# dc25-darknet-dialer.net
KiCad netlist of a schematic drawn in EAGLE
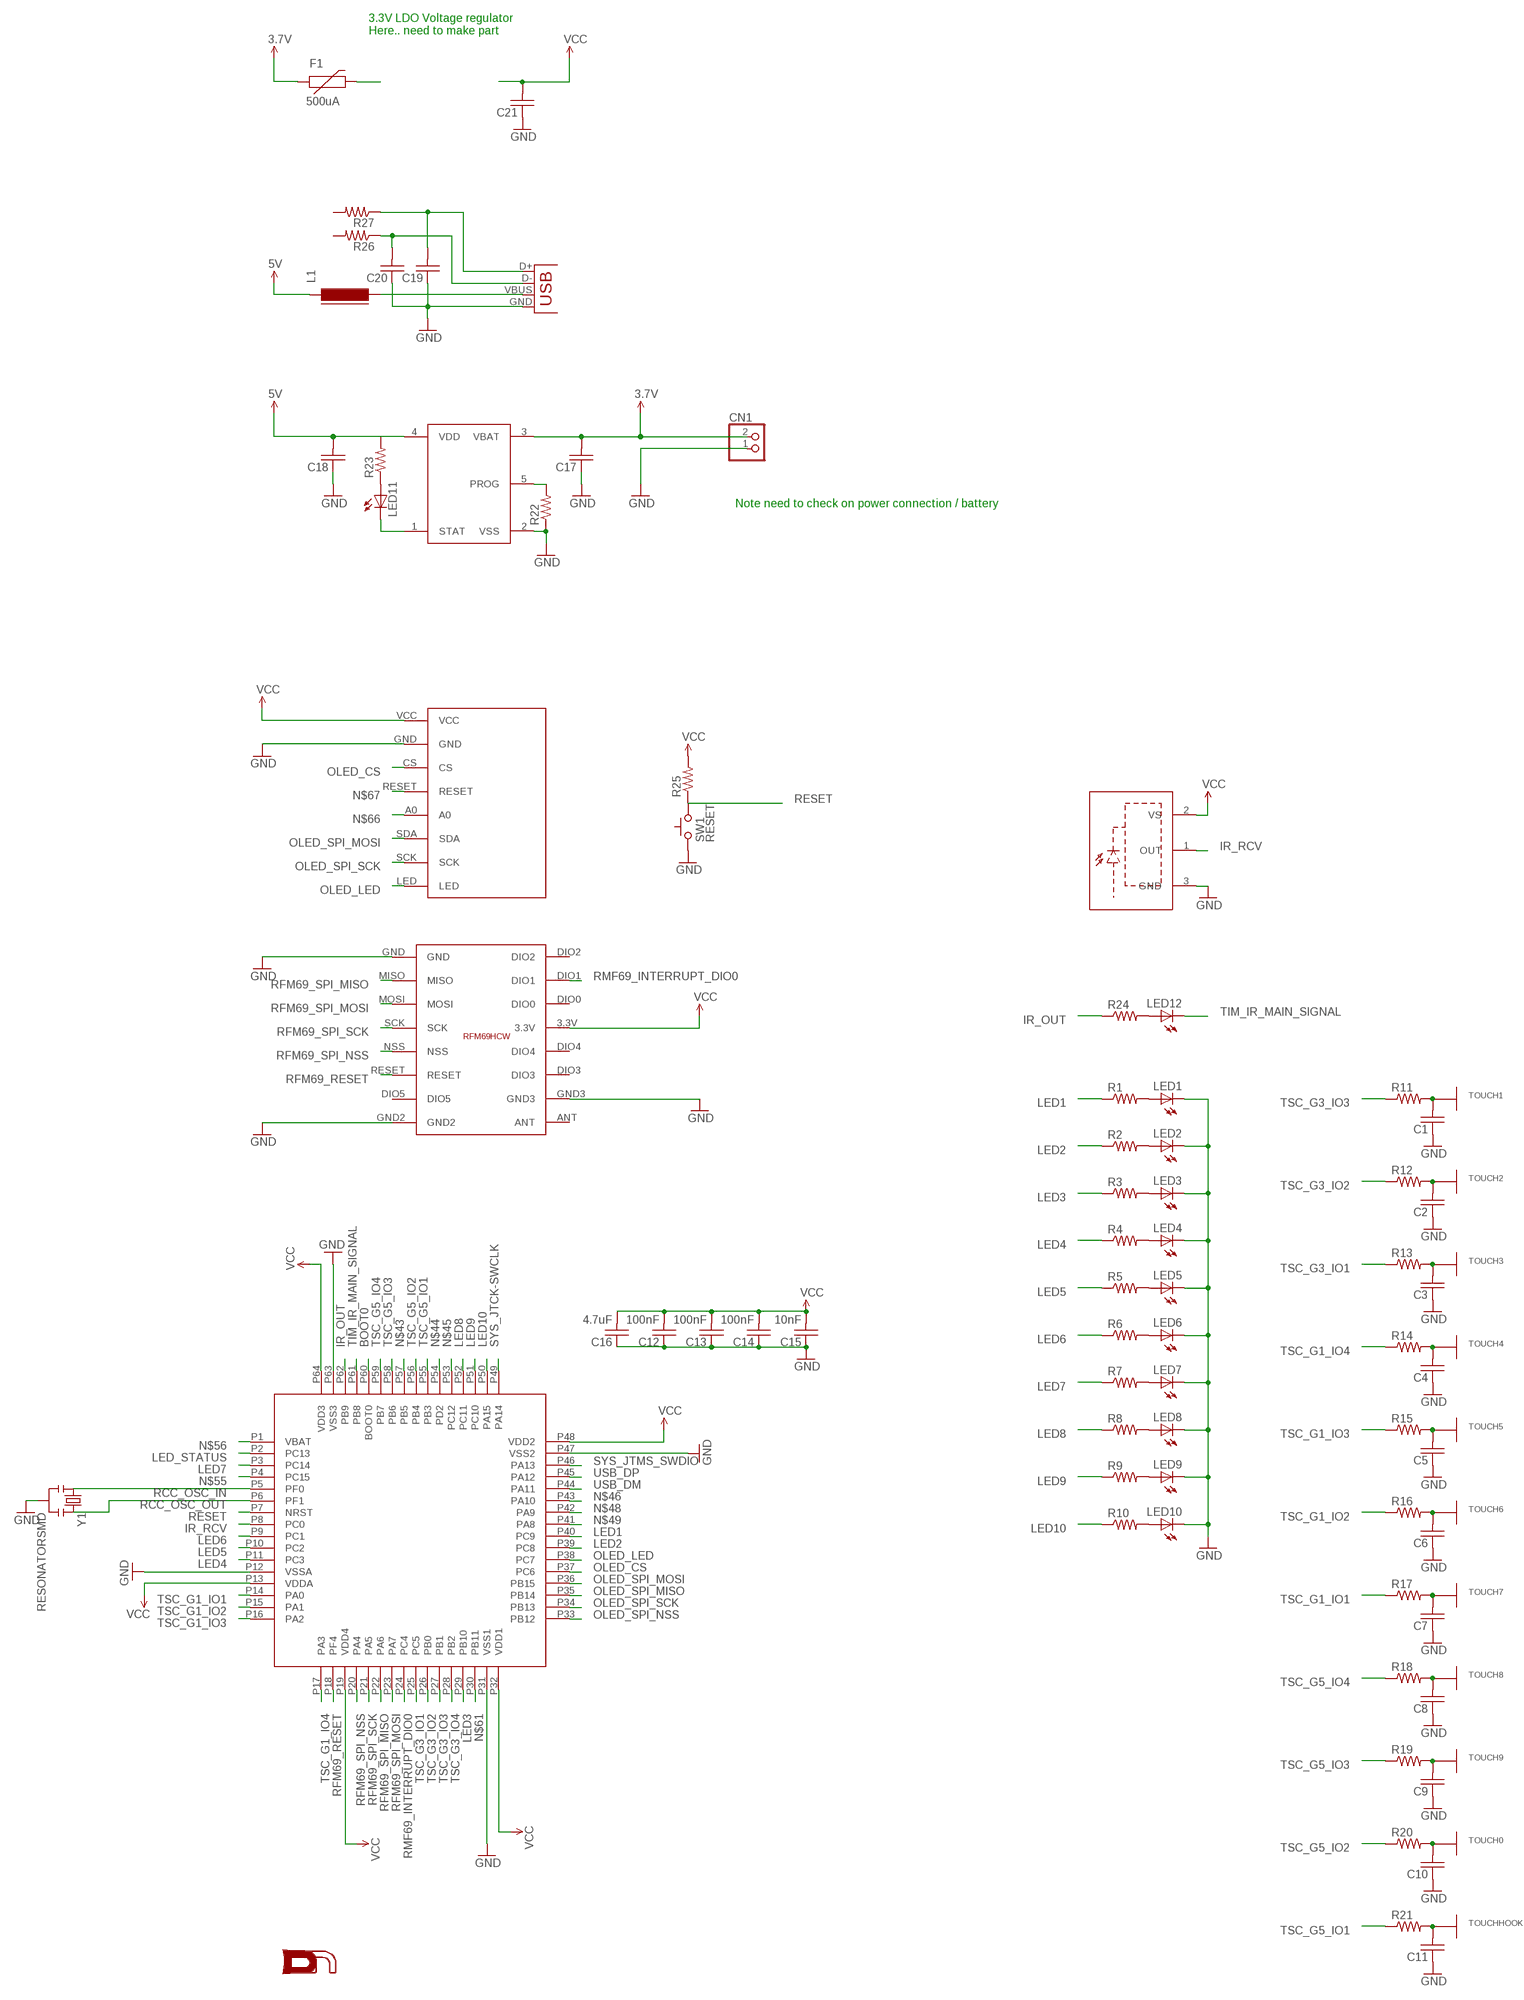
[diagram p0: schematic, sheet 1]

(export (version "E")
  (design (tool "Eeschema 10.0.6"))
  (components
    (comp (ref "C1")
      (value "C-USC0603")
      (footprint "eagle-import:C0603")
      (libsource (lib "eagle-import") (part "C-USC0603"))
    )
    (comp (ref "C2")
      (value "C-USC0603")
      (footprint "eagle-import:C0603")
      (libsource (lib "eagle-import") (part "C-USC0603"))
    )
    (comp (ref "C3")
      (value "C-USC0603")
      (footprint "eagle-import:C0603")
      (libsource (lib "eagle-import") (part "C-USC0603"))
    )
    (comp (ref "C4")
      (value "C-USC0603")
      (footprint "eagle-import:C0603")
      (libsource (lib "eagle-import") (part "C-USC0603"))
    )
    (comp (ref "C5")
      (value "C-USC0603")
      (footprint "eagle-import:C0603")
      (libsource (lib "eagle-import") (part "C-USC0603"))
    )
    (comp (ref "C6")
      (value "C-USC0603")
      (footprint "eagle-import:C0603")
      (libsource (lib "eagle-import") (part "C-USC0603"))
    )
    (comp (ref "C7")
      (value "C-USC0603")
      (footprint "eagle-import:C0603")
      (libsource (lib "eagle-import") (part "C-USC0603"))
    )
    (comp (ref "C8")
      (value "C-USC0603")
      (footprint "eagle-import:C0603")
      (libsource (lib "eagle-import") (part "C-USC0603"))
    )
    (comp (ref "C9")
      (value "C-USC0603")
      (footprint "eagle-import:C0603")
      (libsource (lib "eagle-import") (part "C-USC0603"))
    )
    (comp (ref "C10")
      (value "C-USC0603")
      (footprint "eagle-import:C0603")
      (libsource (lib "eagle-import") (part "C-USC0603"))
    )
    (comp (ref "C11")
      (value "C-USC0603")
      (footprint "eagle-import:C0603")
      (libsource (lib "eagle-import") (part "C-USC0603"))
    )
    (comp (ref "C12")
      (value "100nF")
      (footprint "eagle-import:C0603")
      (libsource (lib "eagle-import") (part "C-USC0603"))
    )
    (comp (ref "C13")
      (value "100nF")
      (footprint "eagle-import:C0603")
      (libsource (lib "eagle-import") (part "C-USC0603"))
    )
    (comp (ref "C14")
      (value "100nF")
      (footprint "eagle-import:C0603")
      (libsource (lib "eagle-import") (part "C-USC0603"))
    )
    (comp (ref "C15")
      (value "10nF")
      (footprint "eagle-import:C0603")
      (libsource (lib "eagle-import") (part "C-USC0603"))
    )
    (comp (ref "C16")
      (value "4.7uF")
      (footprint "eagle-import:C0603")
      (libsource (lib "eagle-import") (part "C-USC0603"))
    )
    (comp (ref "C17")
      (value "C-USC0603")
      (footprint "eagle-import:C0603")
      (libsource (lib "eagle-import") (part "C-USC0603"))
    )
    (comp (ref "C18")
      (value "C-USC0603")
      (footprint "eagle-import:C0603")
      (libsource (lib "eagle-import") (part "C-USC0603"))
    )
    (comp (ref "C19")
      (value "C-USC0603")
      (footprint "eagle-import:C0603")
      (libsource (lib "eagle-import") (part "C-USC0603"))
    )
    (comp (ref "C20")
      (value "C-USC0603")
      (footprint "eagle-import:C0603")
      (libsource (lib "eagle-import") (part "C-USC0603"))
    )
    (comp (ref "C21")
      (value "C-USC0603")
      (footprint "eagle-import:C0603")
      (libsource (lib "eagle-import") (part "C-USC0603"))
    )
    (comp (ref "CN1")
      (value "JST_2PIN-THM-RA")
      (footprint "eagle-import:JST-PH-2-THM-RA")
      (libsource (lib "eagle-import") (part "JST_2PIN-THM-RA"))
    )
    (comp (ref "F1")
      (value "500uA")
      (footprint "eagle-import:PTC-1206")
      (libsource (lib "eagle-import") (part "PTCSMD"))
    )
    (comp (ref "L1")
      (value "FERRITE-0603")
      (footprint "eagle-import:FB603")
      (libsource (lib "eagle-import") (part "FERRITE-0603"))
    )
    (comp (ref "LED1")
      (value "LEDREVERSEMOUNT")
      (footprint "eagle-import:GULLWING_LED")
      (libsource (lib "eagle-import") (part "LEDREVERSEMOUNT"))
    )
    (comp (ref "LED2")
      (value "LEDREVERSEMOUNT")
      (footprint "eagle-import:GULLWING_LED")
      (libsource (lib "eagle-import") (part "LEDREVERSEMOUNT"))
    )
    (comp (ref "LED3")
      (value "LEDREVERSEMOUNT")
      (footprint "eagle-import:GULLWING_LED")
      (libsource (lib "eagle-import") (part "LEDREVERSEMOUNT"))
    )
    (comp (ref "LED4")
      (value "LEDREVERSEMOUNT")
      (footprint "eagle-import:GULLWING_LED")
      (libsource (lib "eagle-import") (part "LEDREVERSEMOUNT"))
    )
    (comp (ref "LED5")
      (value "LEDREVERSEMOUNT")
      (footprint "eagle-import:GULLWING_LED")
      (libsource (lib "eagle-import") (part "LEDREVERSEMOUNT"))
    )
    (comp (ref "LED6")
      (value "LEDREVERSEMOUNT")
      (footprint "eagle-import:GULLWING_LED")
      (libsource (lib "eagle-import") (part "LEDREVERSEMOUNT"))
    )
    (comp (ref "LED7")
      (value "LEDREVERSEMOUNT")
      (footprint "eagle-import:GULLWING_LED")
      (libsource (lib "eagle-import") (part "LEDREVERSEMOUNT"))
    )
    (comp (ref "LED8")
      (value "LEDREVERSEMOUNT")
      (footprint "eagle-import:GULLWING_LED")
      (libsource (lib "eagle-import") (part "LEDREVERSEMOUNT"))
    )
    (comp (ref "LED9")
      (value "LEDREVERSEMOUNT")
      (footprint "eagle-import:GULLWING_LED")
      (libsource (lib "eagle-import") (part "LEDREVERSEMOUNT"))
    )
    (comp (ref "LED10")
      (value "LEDREVERSEMOUNT")
      (footprint "eagle-import:GULLWING_LED")
      (libsource (lib "eagle-import") (part "LEDREVERSEMOUNT"))
    )
    (comp (ref "LED11")
      (value "LED0603")
      (footprint "eagle-import:LED-0603")
      (libsource (lib "eagle-import") (part "LED0603"))
    )
    (comp (ref "LED12")
      (value "LED5MM")
      (footprint "eagle-import:LED5MM")
      (libsource (lib "eagle-import") (part "LED5MM"))
    )
    (comp (ref "R1")
      (value "RESISTOR1206")
      (footprint "eagle-import:1206")
      (libsource (lib "eagle-import") (part "RESISTOR1206"))
    )
    (comp (ref "R2")
      (value "RESISTOR1206")
      (footprint "eagle-import:1206")
      (libsource (lib "eagle-import") (part "RESISTOR1206"))
    )
    (comp (ref "R3")
      (value "RESISTOR1206")
      (footprint "eagle-import:1206")
      (libsource (lib "eagle-import") (part "RESISTOR1206"))
    )
    (comp (ref "R4")
      (value "RESISTOR1206")
      (footprint "eagle-import:1206")
      (libsource (lib "eagle-import") (part "RESISTOR1206"))
    )
    (comp (ref "R5")
      (value "RESISTOR1206")
      (footprint "eagle-import:1206")
      (libsource (lib "eagle-import") (part "RESISTOR1206"))
    )
    (comp (ref "R6")
      (value "RESISTOR1206")
      (footprint "eagle-import:1206")
      (libsource (lib "eagle-import") (part "RESISTOR1206"))
    )
    (comp (ref "R7")
      (value "RESISTOR1206")
      (footprint "eagle-import:1206")
      (libsource (lib "eagle-import") (part "RESISTOR1206"))
    )
    (comp (ref "R8")
      (value "RESISTOR1206")
      (footprint "eagle-import:1206")
      (libsource (lib "eagle-import") (part "RESISTOR1206"))
    )
    (comp (ref "R9")
      (value "RESISTOR1206")
      (footprint "eagle-import:1206")
      (libsource (lib "eagle-import") (part "RESISTOR1206"))
    )
    (comp (ref "R10")
      (value "RESISTOR1206")
      (footprint "eagle-import:1206")
      (libsource (lib "eagle-import") (part "RESISTOR1206"))
    )
    (comp (ref "R11")
      (value "R-US_R0603")
      (footprint "eagle-import:R0603")
      (libsource (lib "eagle-import") (part "R-US_R0603"))
    )
    (comp (ref "R12")
      (value "R-US_R0603")
      (footprint "eagle-import:R0603")
      (libsource (lib "eagle-import") (part "R-US_R0603"))
    )
    (comp (ref "R13")
      (value "R-US_R0603")
      (footprint "eagle-import:R0603")
      (libsource (lib "eagle-import") (part "R-US_R0603"))
    )
    (comp (ref "R14")
      (value "R-US_R0603")
      (footprint "eagle-import:R0603")
      (libsource (lib "eagle-import") (part "R-US_R0603"))
    )
    (comp (ref "R15")
      (value "R-US_R0603")
      (footprint "eagle-import:R0603")
      (libsource (lib "eagle-import") (part "R-US_R0603"))
    )
    (comp (ref "R16")
      (value "R-US_R0603")
      (footprint "eagle-import:R0603")
      (libsource (lib "eagle-import") (part "R-US_R0603"))
    )
    (comp (ref "R17")
      (value "R-US_R0603")
      (footprint "eagle-import:R0603")
      (libsource (lib "eagle-import") (part "R-US_R0603"))
    )
    (comp (ref "R18")
      (value "R-US_R0603")
      (footprint "eagle-import:R0603")
      (libsource (lib "eagle-import") (part "R-US_R0603"))
    )
    (comp (ref "R19")
      (value "R-US_R0603")
      (footprint "eagle-import:R0603")
      (libsource (lib "eagle-import") (part "R-US_R0603"))
    )
    (comp (ref "R20")
      (value "R-US_R0603")
      (footprint "eagle-import:R0603")
      (libsource (lib "eagle-import") (part "R-US_R0603"))
    )
    (comp (ref "R21")
      (value "R-US_R0603")
      (footprint "eagle-import:R0603")
      (libsource (lib "eagle-import") (part "R-US_R0603"))
    )
    (comp (ref "R22")
      (value "R-US_R0603")
      (footprint "eagle-import:R0603")
      (libsource (lib "eagle-import") (part "R-US_R0603"))
    )
    (comp (ref "R23")
      (value "R-US_R0603")
      (footprint "eagle-import:R0603")
      (libsource (lib "eagle-import") (part "R-US_R0603"))
    )
    (comp (ref "R24")
      (value "R-US_0309/12")
      (footprint "eagle-import:0309_12")
      (libsource (lib "eagle-import") (part "R-US_0309/12"))
    )
    (comp (ref "R25")
      (value "R-US_0309/12")
      (footprint "eagle-import:0309_12")
      (libsource (lib "eagle-import") (part "R-US_0309/12"))
    )
    (comp (ref "R26")
      (value "R-US_R0603")
      (footprint "eagle-import:R0603")
      (libsource (lib "eagle-import") (part "R-US_R0603"))
    )
    (comp (ref "R27")
      (value "R-US_R0603")
      (footprint "eagle-import:R0603")
      (libsource (lib "eagle-import") (part "R-US_R0603"))
    )
    (comp (ref "SW1")
      (value "RESET")
      (footprint "eagle-import:TACTILE-2PIN-NARROW")
      (libsource (lib "eagle-import") (part "SWITCH_TACTILETACTILE-2PIN-NARROW"))
    )
    (comp (ref "TOUCH0")
      (value "CAP_TOUCH0")
      (footprint "eagle-import:CAP_TOUCH_PAD_0")
      (libsource (lib "eagle-import") (part "CAP_TOUCH0"))
    )
    (comp (ref "TOUCH1")
      (value "CAP_TOUCH1")
      (footprint "eagle-import:CAP_TOUCH_PAD_1")
      (libsource (lib "eagle-import") (part "CAP_TOUCH1"))
    )
    (comp (ref "TOUCH2")
      (value "CAP_TOUCH2")
      (footprint "eagle-import:CAP_TOUCH_PAD_2")
      (libsource (lib "eagle-import") (part "CAP_TOUCH2"))
    )
    (comp (ref "TOUCH3")
      (value "CAP_TOUCH3")
      (footprint "eagle-import:CAP_TOUCH_PAD_3")
      (libsource (lib "eagle-import") (part "CAP_TOUCH3"))
    )
    (comp (ref "TOUCH4")
      (value "CAP_TOUCH4")
      (footprint "eagle-import:CAP_TOUCH_PAD_4")
      (libsource (lib "eagle-import") (part "CAP_TOUCH4"))
    )
    (comp (ref "TOUCH5")
      (value "CAP_TOUCH5")
      (footprint "eagle-import:CAP_TOUCH_PAD_5")
      (libsource (lib "eagle-import") (part "CAP_TOUCH5"))
    )
    (comp (ref "TOUCH6")
      (value "CAP_TOUCH6")
      (footprint "eagle-import:CAP_TOUCH_PAD_6")
      (libsource (lib "eagle-import") (part "CAP_TOUCH6"))
    )
    (comp (ref "TOUCH7")
      (value "CAP_TOUCH7")
      (footprint "eagle-import:CAP_TOUCH_PAD_7")
      (libsource (lib "eagle-import") (part "CAP_TOUCH7"))
    )
    (comp (ref "TOUCH8")
      (value "CAP_TOUCH8")
      (footprint "eagle-import:CAP_TOUCH_PAD_8")
      (libsource (lib "eagle-import") (part "CAP_TOUCH8"))
    )
    (comp (ref "TOUCH9")
      (value "CAP_TOUCH9")
      (footprint "eagle-import:CAP_TOUCH_PAD_9")
      (libsource (lib "eagle-import") (part "CAP_TOUCH9"))
    )
    (comp (ref "TOUCHHOOK")
      (value "CAP_TOUCHHOOK")
      (footprint "eagle-import:CAP_TOUCH_PAD_HOOK")
      (libsource (lib "eagle-import") (part "CAP_TOUCHHOOK"))
    )
    (comp (ref "U$1")
      (value "DN_LOGO")
      (footprint "eagle-import:DN_LOGO")
      (libsource (lib "eagle-import") (part "DN_LOGO"))
    )
    (comp (ref "U$2")
      (value "STM32F302XC")
      (footprint "eagle-import:LQFP64")
      (libsource (lib "eagle-import") (part "STM32F302XC"))
    )
    (comp (ref "U$11")
      (value "DS21984E")
      (footprint "eagle-import:SOT23-5")
      (libsource (lib "eagle-import") (part "DS21984E"))
    )
    (comp (ref "U$12")
      (value "COLOR_LCD_MODULE")
      (footprint "eagle-import:COLOR_LCD_DISPLAY")
      (libsource (lib "eagle-import") (part "COLOR_LCD_MODULE"))
    )
    (comp (ref "U$15")
      (value "RFM69HCWRFN69HCWSMD")
      (footprint "eagle-import:16PIN-PCB-SMD")
      (libsource (lib "eagle-import") (part "RFM69HCWRFN69HCWSMD"))
    )
    (comp (ref "U$17")
      (value "SOP22")
      (footprint "eagle-import:IR-MODULE")
      (libsource (lib "eagle-import") (part "SOP22"))
    )
    (comp (ref "X1")
      (value "USB-MICROB")
      (footprint "eagle-import:USB-MICROB")
      (libsource (lib "eagle-import") (part "USB-MICROB"))
    )
    (comp (ref "Y1")
      (value "RESONATORSMD")
      (footprint "eagle-import:RESONATOR-SMD")
      (libsource (lib "eagle-import") (part "RESONATORSMD"))
    )
  )
  (nets
    (net (code "1") (name "/BOOT0") (class "Default")
      (node (ref "U$2") (pin "P60") (pinfunction "BOOT0_P60") (pintype "bidirectional"))
    )
    (net (code "2") (name "/IR_OUT") (class "Default")
      (node (ref "R24") (pin "1") (pinfunction "1_1") (pintype "passive"))
      (node (ref "U$2") (pin "P62") (pinfunction "PB9_P62") (pintype "bidirectional"))
    )
    (net (code "3") (name "/IR_RCV") (class "Default")
      (node (ref "U$17") (pin "1") (pinfunction "OUT_1") (pintype "bidirectional"))
      (node (ref "U$2") (pin "P8") (pinfunction "PC0_P8") (pintype "bidirectional"))
    )
    (net (code "4") (name "/LED1") (class "Default")
      (node (ref "R1") (pin "1") (pinfunction "1_1") (pintype "passive"))
      (node (ref "U$2") (pin "P40") (pinfunction "PC9_P40") (pintype "bidirectional"))
    )
    (net (code "5") (name "/LED2") (class "Default")
      (node (ref "R2") (pin "1") (pinfunction "1_1") (pintype "passive"))
      (node (ref "U$2") (pin "P39") (pinfunction "PC8_P39") (pintype "bidirectional"))
    )
    (net (code "6") (name "/LED3") (class "Default")
      (node (ref "R3") (pin "1") (pinfunction "1_1") (pintype "passive"))
      (node (ref "U$2") (pin "P29") (pinfunction "PB10_P29") (pintype "bidirectional"))
    )
    (net (code "7") (name "/LED4") (class "Default")
      (node (ref "R4") (pin "1") (pinfunction "1_1") (pintype "passive"))
      (node (ref "U$2") (pin "P11") (pinfunction "PC3_P11") (pintype "bidirectional"))
    )
    (net (code "8") (name "/LED5") (class "Default")
      (node (ref "R5") (pin "1") (pinfunction "1_1") (pintype "passive"))
      (node (ref "U$2") (pin "P10") (pinfunction "PC2_P10") (pintype "bidirectional"))
    )
    (net (code "9") (name "/LED6") (class "Default")
      (node (ref "R6") (pin "1") (pinfunction "1_1") (pintype "passive"))
      (node (ref "U$2") (pin "P9") (pinfunction "PC1_P9") (pintype "bidirectional"))
    )
    (net (code "10") (name "/LED7") (class "Default")
      (node (ref "R7") (pin "1") (pinfunction "1_1") (pintype "passive"))
      (node (ref "U$2") (pin "P3") (pinfunction "PC14_P3") (pintype "bidirectional"))
    )
    (net (code "11") (name "/LED8") (class "Default")
      (node (ref "R8") (pin "1") (pinfunction "1_1") (pintype "passive"))
      (node (ref "U$2") (pin "P52") (pinfunction "PC11_P52") (pintype "bidirectional"))
    )
    (net (code "12") (name "/LED9") (class "Default")
      (node (ref "R9") (pin "1") (pinfunction "1_1") (pintype "passive"))
      (node (ref "U$2") (pin "P51") (pinfunction "PC10_P51") (pintype "bidirectional"))
    )
    (net (code "13") (name "/LED10") (class "Default")
      (node (ref "R10") (pin "1") (pinfunction "1_1") (pintype "passive"))
      (node (ref "U$2") (pin "P50") (pinfunction "PA15_P50") (pintype "bidirectional"))
    )
    (net (code "14") (name "/LED_STATUS") (class "Default")
      (node (ref "U$2") (pin "P2") (pinfunction "PC13_P2") (pintype "bidirectional"))
    )
    (net (code "15") (name "/N$43") (class "Default")
      (node (ref "U$2") (pin "P57") (pinfunction "PB5_P57") (pintype "bidirectional"))
    )
    (net (code "16") (name "/N$44") (class "Default")
      (node (ref "U$2") (pin "P54") (pinfunction "PD2_P54") (pintype "bidirectional"))
    )
    (net (code "17") (name "/N$45") (class "Default")
      (node (ref "U$2") (pin "P53") (pinfunction "PC12_P53") (pintype "bidirectional"))
    )
    (net (code "18") (name "/N$46") (class "Default")
      (node (ref "U$2") (pin "P43") (pinfunction "PA10_P43") (pintype "bidirectional"))
    )
    (net (code "19") (name "/N$48") (class "Default")
      (node (ref "U$2") (pin "P42") (pinfunction "PA9_P42") (pintype "bidirectional"))
    )
    (net (code "20") (name "/N$49") (class "Default")
      (node (ref "U$2") (pin "P41") (pinfunction "PA8_P41") (pintype "bidirectional"))
    )
    (net (code "21") (name "/N$55") (class "Default")
      (node (ref "U$2") (pin "P4") (pinfunction "PC15_P4") (pintype "bidirectional"))
    )
    (net (code "22") (name "/N$56") (class "Default")
      (node (ref "U$2") (pin "P1") (pinfunction "VBAT_P1") (pintype "bidirectional"))
    )
    (net (code "23") (name "/N$61") (class "Default")
      (node (ref "U$2") (pin "P30") (pinfunction "PB11_P30") (pintype "bidirectional"))
    )
    (net (code "24") (name "/N$66") (class "Default")
      (node (ref "U$12") (pin "A0") (pinfunction "A0_A0") (pintype "bidirectional"))
    )
    (net (code "25") (name "/N$67") (class "Default")
      (node (ref "U$12") (pin "RESET") (pinfunction "RESET_RESET") (pintype "bidirectional"))
    )
    (net (code "26") (name "/OLED_CS") (class "Default")
      (node (ref "U$12") (pin "CS") (pinfunction "CS_CS") (pintype "bidirectional"))
      (node (ref "U$2") (pin "P37") (pinfunction "PC6_P37") (pintype "bidirectional"))
    )
    (net (code "27") (name "/OLED_LED") (class "Default")
      (node (ref "U$12") (pin "LED") (pinfunction "LED_LED") (pintype "bidirectional"))
      (node (ref "U$2") (pin "P38") (pinfunction "PC7_P38") (pintype "bidirectional"))
    )
    (net (code "28") (name "/OLED_SPI_MISO") (class "Default")
      (node (ref "U$2") (pin "P35") (pinfunction "PB14_P35") (pintype "bidirectional"))
    )
    (net (code "29") (name "/OLED_SPI_MOSI") (class "Default")
      (node (ref "U$12") (pin "SDA") (pinfunction "SDA_SDA") (pintype "bidirectional"))
      (node (ref "U$2") (pin "P36") (pinfunction "PB15_P36") (pintype "bidirectional"))
    )
    (net (code "30") (name "/OLED_SPI_NSS") (class "Default")
      (node (ref "U$2") (pin "P33") (pinfunction "PB12_P33") (pintype "bidirectional"))
    )
    (net (code "31") (name "/OLED_SPI_SCK") (class "Default")
      (node (ref "U$12") (pin "SCK") (pinfunction "SCK_SCK") (pintype "bidirectional"))
      (node (ref "U$2") (pin "P34") (pinfunction "PB13_P34") (pintype "bidirectional"))
    )
    (net (code "32") (name "/RCC_OSC_IN") (class "Default")
      (node (ref "U$2") (pin "P5") (pinfunction "PF0_P5") (pintype "bidirectional"))
      (node (ref "Y1") (pin "1") (pinfunction "1_1") (pintype "passive"))
    )
    (net (code "33") (name "/RCC_OSC_OUT") (class "Default")
      (node (ref "U$2") (pin "P6") (pinfunction "PF1_P6") (pintype "bidirectional"))
      (node (ref "Y1") (pin "3") (pinfunction "3_3") (pintype "passive"))
    )
    (net (code "34") (name "/RESET") (class "Default")
      (node (ref "R25") (pin "1") (pinfunction "1_1") (pintype "passive"))
      (node (ref "SW1") (pin "P$1") (pinfunction "A_P$1") (pintype "passive"))
      (node (ref "U$2") (pin "P7") (pinfunction "NRST_P7") (pintype "bidirectional"))
    )
    (net (code "35") (name "/RFM69_RESET") (class "Default")
      (node (ref "U$15") (pin "RESET") (pinfunction "RESET_RESET") (pintype "bidirectional"))
      (node (ref "U$2") (pin "P18") (pinfunction "PF4_P18") (pintype "bidirectional"))
    )
    (net (code "36") (name "/RFM69_SPI_MISO") (class "Default")
      (node (ref "U$15") (pin "MISO") (pinfunction "MISO_MISO") (pintype "bidirectional"))
      (node (ref "U$2") (pin "P22") (pinfunction "PA6_P22") (pintype "bidirectional"))
    )
    (net (code "37") (name "/RFM69_SPI_MOSI") (class "Default")
      (node (ref "U$15") (pin "MOSI") (pinfunction "MOSI_MOSI") (pintype "bidirectional"))
      (node (ref "U$2") (pin "P23") (pinfunction "PA7_P23") (pintype "bidirectional"))
    )
    (net (code "38") (name "/RFM69_SPI_NSS") (class "Default")
      (node (ref "U$15") (pin "NSS") (pinfunction "NSS_NSS") (pintype "bidirectional"))
      (node (ref "U$2") (pin "P20") (pinfunction "PA4_P20") (pintype "bidirectional"))
    )
    (net (code "39") (name "/RFM69_SPI_SCK") (class "Default")
      (node (ref "U$15") (pin "SCK") (pinfunction "SCK_SCK") (pintype "bidirectional"))
      (node (ref "U$2") (pin "P21") (pinfunction "PA5_P21") (pintype "bidirectional"))
    )
    (net (code "40") (name "/RMF69_INTERRUPT_DIO0") (class "Default")
      (node (ref "U$15") (pin "DIO1") (pinfunction "DIO1_DIO1") (pintype "bidirectional"))
      (node (ref "U$2") (pin "P24") (pinfunction "PC4_P24") (pintype "bidirectional"))
    )
    (net (code "41") (name "/SYS_JTCK-SWCLK") (class "Default")
      (node (ref "U$2") (pin "P49") (pinfunction "PA14_P49") (pintype "bidirectional"))
    )
    (net (code "42") (name "/SYS_JTMS_SWDIO") (class "Default")
      (node (ref "U$2") (pin "P46") (pinfunction "PA13_P46") (pintype "bidirectional"))
    )
    (net (code "43") (name "/TIM_IR_MAIN_SIGNAL") (class "Default")
      (node (ref "LED12") (pin "K") (pinfunction "C_K") (pintype "output"))
      (node (ref "U$2") (pin "P61") (pinfunction "PB8_P61") (pintype "bidirectional"))
    )
    (net (code "44") (name "/TSC_G1_IO1") (class "Default")
      (node (ref "R17") (pin "1") (pinfunction "1_1") (pintype "passive"))
      (node (ref "U$2") (pin "P14") (pinfunction "PA0_P14") (pintype "bidirectional"))
    )
    (net (code "45") (name "/TSC_G1_IO2") (class "Default")
      (node (ref "R16") (pin "1") (pinfunction "1_1") (pintype "passive"))
      (node (ref "U$2") (pin "P15") (pinfunction "PA1_P15") (pintype "bidirectional"))
    )
    (net (code "46") (name "/TSC_G1_IO3") (class "Default")
      (node (ref "R15") (pin "1") (pinfunction "1_1") (pintype "passive"))
      (node (ref "U$2") (pin "P16") (pinfunction "PA2_P16") (pintype "bidirectional"))
    )
    (net (code "47") (name "/TSC_G1_IO4") (class "Default")
      (node (ref "R14") (pin "1") (pinfunction "1_1") (pintype "passive"))
      (node (ref "U$2") (pin "P17") (pinfunction "PA3_P17") (pintype "bidirectional"))
    )
    (net (code "48") (name "/TSC_G3_IO1") (class "Default")
      (node (ref "R13") (pin "1") (pinfunction "1_1") (pintype "passive"))
      (node (ref "U$2") (pin "P25") (pinfunction "PC5_P25") (pintype "bidirectional"))
    )
    (net (code "49") (name "/TSC_G3_IO2") (class "Default")
      (node (ref "R12") (pin "1") (pinfunction "1_1") (pintype "passive"))
      (node (ref "U$2") (pin "P26") (pinfunction "PB0_P26") (pintype "bidirectional"))
    )
    (net (code "50") (name "/TSC_G3_IO3") (class "Default")
      (node (ref "R11") (pin "1") (pinfunction "1_1") (pintype "passive"))
      (node (ref "U$2") (pin "P27") (pinfunction "PB1_P27") (pintype "bidirectional"))
    )
    (net (code "51") (name "/TSC_G3_IO4") (class "Default")
      (node (ref "U$2") (pin "P28") (pinfunction "PB2_P28") (pintype "bidirectional"))
    )
    (net (code "52") (name "/TSC_G5_IO1") (class "Default")
      (node (ref "R21") (pin "1") (pinfunction "1_1") (pintype "passive"))
      (node (ref "U$2") (pin "P55") (pinfunction "PB3_P55") (pintype "bidirectional"))
    )
    (net (code "53") (name "/TSC_G5_IO2") (class "Default")
      (node (ref "R20") (pin "1") (pinfunction "1_1") (pintype "passive"))
      (node (ref "U$2") (pin "P56") (pinfunction "PB4_P56") (pintype "bidirectional"))
    )
    (net (code "54") (name "/TSC_G5_IO3") (class "Default")
      (node (ref "R19") (pin "1") (pinfunction "1_1") (pintype "passive"))
      (node (ref "U$2") (pin "P58") (pinfunction "PB6_P58") (pintype "bidirectional"))
    )
    (net (code "55") (name "/TSC_G5_IO4") (class "Default")
      (node (ref "R18") (pin "1") (pinfunction "1_1") (pintype "passive"))
      (node (ref "U$2") (pin "P59") (pinfunction "PB7_P59") (pintype "bidirectional"))
    )
    (net (code "56") (name "/USB_DM") (class "Default")
      (node (ref "U$2") (pin "P44") (pinfunction "PA11_P44") (pintype "bidirectional"))
    )
    (net (code "57") (name "/USB_DP") (class "Default")
      (node (ref "U$2") (pin "P45") (pinfunction "PA12_P45") (pintype "bidirectional"))
    )
    (net (code "58") (name "3.7V") (class "Default")
      (node (ref "C17") (pin "2") (pinfunction "2_2") (pintype "passive"))
      (node (ref "CN1") (pin "2") (pinfunction "1_2") (pintype "passive"))
      (node (ref "F1") (pin "1") (pinfunction "1_1") (pintype "bidirectional"))
      (node (ref "U$11") (pin "3") (pinfunction "VBAT_3") (pintype "bidirectional"))
    )
    (net (code "59") (name "5V") (class "Default")
      (node (ref "C18") (pin "2") (pinfunction "2_2") (pintype "passive"))
      (node (ref "L1") (pin "1") (pinfunction "1_1") (pintype "passive"))
      (node (ref "R23") (pin "2") (pinfunction "2_2") (pintype "passive"))
      (node (ref "U$11") (pin "4") (pinfunction "VDD_4") (pintype "bidirectional"))
    )
    (net (code "60") (name "GND") (class "Default")
      (node (ref "C1") (pin "1") (pinfunction "1_1") (pintype "passive"))
      (node (ref "C10") (pin "1") (pinfunction "1_1") (pintype "passive"))
      (node (ref "C11") (pin "1") (pinfunction "1_1") (pintype "passive"))
      (node (ref "C12") (pin "1") (pinfunction "1_1") (pintype "passive"))
      (node (ref "C13") (pin "1") (pinfunction "1_1") (pintype "passive"))
      (node (ref "C14") (pin "1") (pinfunction "1_1") (pintype "passive"))
      (node (ref "C15") (pin "1") (pinfunction "1_1") (pintype "passive"))
      (node (ref "C16") (pin "1") (pinfunction "1_1") (pintype "passive"))
      (node (ref "C17") (pin "1") (pinfunction "1_1") (pintype "passive"))
      (node (ref "C18") (pin "1") (pinfunction "1_1") (pintype "passive"))
      (node (ref "C19") (pin "1") (pinfunction "1_1") (pintype "passive"))
      (node (ref "C2") (pin "1") (pinfunction "1_1") (pintype "passive"))
      (node (ref "C20") (pin "1") (pinfunction "1_1") (pintype "passive"))
      (node (ref "C21") (pin "1") (pinfunction "1_1") (pintype "passive"))
      (node (ref "C3") (pin "1") (pinfunction "1_1") (pintype "passive"))
      (node (ref "C4") (pin "1") (pinfunction "1_1") (pintype "passive"))
      (node (ref "C5") (pin "1") (pinfunction "1_1") (pintype "passive"))
      (node (ref "C6") (pin "1") (pinfunction "1_1") (pintype "passive"))
      (node (ref "C7") (pin "1") (pinfunction "1_1") (pintype "passive"))
      (node (ref "C8") (pin "1") (pinfunction "1_1") (pintype "passive"))
      (node (ref "C9") (pin "1") (pinfunction "1_1") (pintype "passive"))
      (node (ref "CN1") (pin "1") (pinfunction "2_1") (pintype "passive"))
      (node (ref "LED1") (pin "C") (pinfunction "C_C") (pintype "output"))
      (node (ref "LED10") (pin "C") (pinfunction "C_C") (pintype "output"))
      (node (ref "LED2") (pin "C") (pinfunction "C_C") (pintype "output"))
      (node (ref "LED3") (pin "C") (pinfunction "C_C") (pintype "output"))
      (node (ref "LED4") (pin "C") (pinfunction "C_C") (pintype "output"))
      (node (ref "LED5") (pin "C") (pinfunction "C_C") (pintype "output"))
      (node (ref "LED6") (pin "C") (pinfunction "C_C") (pintype "output"))
      (node (ref "LED7") (pin "C") (pinfunction "C_C") (pintype "output"))
      (node (ref "LED8") (pin "C") (pinfunction "C_C") (pintype "output"))
      (node (ref "LED9") (pin "C") (pinfunction "C_C") (pintype "output"))
      (node (ref "R22") (pin "1") (pinfunction "1_1") (pintype "passive"))
      (node (ref "SW1") (pin "P$2") (pinfunction "C_P$2") (pintype "passive"))
      (node (ref "U$11") (pin "2") (pinfunction "VSS_2") (pintype "bidirectional"))
      (node (ref "U$12") (pin "GND") (pinfunction "GND_GND") (pintype "bidirectional"))
      (node (ref "U$15") (pin "GND") (pinfunction "GND_GND") (pintype "bidirectional"))
      (node (ref "U$15") (pin "GND2") (pinfunction "GND2_GND2") (pintype "bidirectional"))
      (node (ref "U$15") (pin "GND3") (pinfunction "GND3_GND3") (pintype "bidirectional"))
      (node (ref "U$17") (pin "3") (pinfunction "GND_3") (pintype "bidirectional"))
      (node (ref "U$2") (pin "P12") (pinfunction "VSSA_P12") (pintype "bidirectional"))
      (node (ref "U$2") (pin "P31") (pinfunction "VSS1_P31") (pintype "bidirectional"))
      (node (ref "U$2") (pin "P47") (pinfunction "VSS2_P47") (pintype "bidirectional"))
      (node (ref "U$2") (pin "P63") (pinfunction "VSS3_P63") (pintype "bidirectional"))
      (node (ref "X1") (pin "GND") (pinfunction "GND_GND") (pintype "bidirectional"))
      (node (ref "Y1") (pin "2") (pinfunction "2_2") (pintype "passive"))
    )
    (net (code "61") (name "Net-(C19-Pad2)") (class "Default")
      (node (ref "C19") (pin "2") (pinfunction "2_2") (pintype "passive"))
      (node (ref "R27") (pin "1") (pinfunction "1_1") (pintype "passive"))
      (node (ref "X1") (pin "D+") (pinfunction "D+_D+") (pintype "bidirectional"))
    )
    (net (code "62") (name "Net-(C20-Pad2)") (class "Default")
      (node (ref "C20") (pin "2") (pinfunction "2_2") (pintype "passive"))
      (node (ref "R26") (pin "1") (pinfunction "1_1") (pintype "passive"))
      (node (ref "X1") (pin "D-") (pinfunction "D-_D-") (pintype "bidirectional"))
    )
    (net (code "63") (name "Net-(L1-Pad2)") (class "Default")
      (node (ref "L1") (pin "2") (pinfunction "2_2") (pintype "passive"))
      (node (ref "X1") (pin "VBUS") (pinfunction "VBUS_VBUS") (pintype "bidirectional"))
    )
    (net (code "64") (name "Net-(LED1-PadA)") (class "Default")
      (node (ref "LED1") (pin "A") (pinfunction "A_A") (pintype "input"))
      (node (ref "R1") (pin "2") (pinfunction "2_2") (pintype "passive"))
    )
    (net (code "65") (name "Net-(LED2-PadA)") (class "Default")
      (node (ref "LED2") (pin "A") (pinfunction "A_A") (pintype "input"))
      (node (ref "R2") (pin "2") (pinfunction "2_2") (pintype "passive"))
    )
    (net (code "66") (name "Net-(LED3-PadA)") (class "Default")
      (node (ref "LED3") (pin "A") (pinfunction "A_A") (pintype "input"))
      (node (ref "R3") (pin "2") (pinfunction "2_2") (pintype "passive"))
    )
    (net (code "67") (name "Net-(LED4-PadA)") (class "Default")
      (node (ref "LED4") (pin "A") (pinfunction "A_A") (pintype "input"))
      (node (ref "R4") (pin "2") (pinfunction "2_2") (pintype "passive"))
    )
    (net (code "68") (name "Net-(LED5-PadA)") (class "Default")
      (node (ref "LED5") (pin "A") (pinfunction "A_A") (pintype "input"))
      (node (ref "R5") (pin "2") (pinfunction "2_2") (pintype "passive"))
    )
    (net (code "69") (name "Net-(LED6-PadA)") (class "Default")
      (node (ref "LED6") (pin "A") (pinfunction "A_A") (pintype "input"))
      (node (ref "R6") (pin "2") (pinfunction "2_2") (pintype "passive"))
    )
    (net (code "70") (name "Net-(LED7-PadA)") (class "Default")
      (node (ref "LED7") (pin "A") (pinfunction "A_A") (pintype "input"))
      (node (ref "R7") (pin "2") (pinfunction "2_2") (pintype "passive"))
    )
    (net (code "71") (name "Net-(LED8-PadA)") (class "Default")
      (node (ref "LED8") (pin "A") (pinfunction "A_A") (pintype "input"))
      (node (ref "R8") (pin "2") (pinfunction "2_2") (pintype "passive"))
    )
    (net (code "72") (name "Net-(LED9-PadA)") (class "Default")
      (node (ref "LED9") (pin "A") (pinfunction "A_A") (pintype "input"))
      (node (ref "R9") (pin "2") (pinfunction "2_2") (pintype "passive"))
    )
    (net (code "73") (name "Net-(LED10-PadA)") (class "Default")
      (node (ref "LED10") (pin "A") (pinfunction "A_A") (pintype "input"))
      (node (ref "R10") (pin "2") (pinfunction "2_2") (pintype "passive"))
    )
    (net (code "74") (name "Net-(LED11-PadA)") (class "Default")
      (node (ref "LED11") (pin "A") (pinfunction "A_A") (pintype "input"))
      (node (ref "R23") (pin "1") (pinfunction "1_1") (pintype "passive"))
    )
    (net (code "75") (name "Net-(LED12-PadA)") (class "Default")
      (node (ref "LED12") (pin "A") (pinfunction "A_A") (pintype "input"))
      (node (ref "R24") (pin "2") (pinfunction "2_2") (pintype "passive"))
    )
    (net (code "76") (name "Net-(TOUCH0-TOUCH)") (class "Default")
      (node (ref "C10") (pin "2") (pinfunction "2_2") (pintype "passive"))
      (node (ref "R20") (pin "2") (pinfunction "2_2") (pintype "passive"))
      (node (ref "TOUCH0") (pin "PAD") (pinfunction "TOUCH_PAD") (pintype "bidirectional"))
    )
    (net (code "77") (name "Net-(TOUCH1-TOUCH)") (class "Default")
      (node (ref "C1") (pin "2") (pinfunction "2_2") (pintype "passive"))
      (node (ref "R11") (pin "2") (pinfunction "2_2") (pintype "passive"))
      (node (ref "TOUCH1") (pin "PAD") (pinfunction "TOUCH_PAD") (pintype "bidirectional"))
    )
    (net (code "78") (name "Net-(TOUCH2-TOUCH)") (class "Default")
      (node (ref "C2") (pin "2") (pinfunction "2_2") (pintype "passive"))
      (node (ref "R12") (pin "2") (pinfunction "2_2") (pintype "passive"))
      (node (ref "TOUCH2") (pin "PAD") (pinfunction "TOUCH_PAD") (pintype "bidirectional"))
    )
    (net (code "79") (name "Net-(TOUCH3-TOUCH)") (class "Default")
      (node (ref "C3") (pin "2") (pinfunction "2_2") (pintype "passive"))
      (node (ref "R13") (pin "2") (pinfunction "2_2") (pintype "passive"))
      (node (ref "TOUCH3") (pin "PAD") (pinfunction "TOUCH_PAD") (pintype "bidirectional"))
    )
    (net (code "80") (name "Net-(TOUCH4-TOUCH)") (class "Default")
      (node (ref "C4") (pin "2") (pinfunction "2_2") (pintype "passive"))
      (node (ref "R14") (pin "2") (pinfunction "2_2") (pintype "passive"))
      (node (ref "TOUCH4") (pin "PAD") (pinfunction "TOUCH_PAD") (pintype "bidirectional"))
    )
    (net (code "81") (name "Net-(TOUCH5-TOUCH)") (class "Default")
      (node (ref "C5") (pin "2") (pinfunction "2_2") (pintype "passive"))
      (node (ref "R15") (pin "2") (pinfunction "2_2") (pintype "passive"))
      (node (ref "TOUCH5") (pin "PAD") (pinfunction "TOUCH_PAD") (pintype "bidirectional"))
    )
    (net (code "82") (name "Net-(TOUCH6-TOUCH)") (class "Default")
      (node (ref "C6") (pin "2") (pinfunction "2_2") (pintype "passive"))
      (node (ref "R16") (pin "2") (pinfunction "2_2") (pintype "passive"))
      (node (ref "TOUCH6") (pin "PAD") (pinfunction "TOUCH_PAD") (pintype "bidirectional"))
    )
    (net (code "83") (name "Net-(TOUCH7-TOUCH)") (class "Default")
      (node (ref "C7") (pin "2") (pinfunction "2_2") (pintype "passive"))
      (node (ref "R17") (pin "2") (pinfunction "2_2") (pintype "passive"))
      (node (ref "TOUCH7") (pin "PAD") (pinfunction "TOUCH_PAD") (pintype "bidirectional"))
    )
    (net (code "84") (name "Net-(TOUCH8-TOUCH)") (class "Default")
      (node (ref "C8") (pin "2") (pinfunction "2_2") (pintype "passive"))
      (node (ref "R18") (pin "2") (pinfunction "2_2") (pintype "passive"))
      (node (ref "TOUCH8") (pin "PAD") (pinfunction "TOUCH_PAD") (pintype "bidirectional"))
    )
    (net (code "85") (name "Net-(TOUCH9-TOUCH)") (class "Default")
      (node (ref "C9") (pin "2") (pinfunction "2_2") (pintype "passive"))
      (node (ref "R19") (pin "2") (pinfunction "2_2") (pintype "passive"))
      (node (ref "TOUCH9") (pin "PAD") (pinfunction "TOUCH_PAD") (pintype "bidirectional"))
    )
    (net (code "86") (name "Net-(TOUCHHOOK-TOUCH)") (class "Default")
      (node (ref "C11") (pin "2") (pinfunction "2_2") (pintype "passive"))
      (node (ref "R21") (pin "2") (pinfunction "2_2") (pintype "passive"))
      (node (ref "TOUCHHOOK") (pin "P$1") (pinfunction "TOUCH_P$1") (pintype "bidirectional"))
    )
    (net (code "87") (name "Net-(U$11-PROG)") (class "Default")
      (node (ref "R22") (pin "2") (pinfunction "2_2") (pintype "passive"))
      (node (ref "U$11") (pin "5") (pinfunction "PROG_5") (pintype "bidirectional"))
    )
    (net (code "88") (name "Net-(U$11-STAT)") (class "Default")
      (node (ref "LED11") (pin "C") (pinfunction "C_C") (pintype "output"))
      (node (ref "U$11") (pin "1") (pinfunction "STAT_1") (pintype "bidirectional"))
    )
    (net (code "89") (name "VCC") (class "Default")
      (node (ref "C12") (pin "2") (pinfunction "2_2") (pintype "passive"))
      (node (ref "C13") (pin "2") (pinfunction "2_2") (pintype "passive"))
      (node (ref "C14") (pin "2") (pinfunction "2_2") (pintype "passive"))
      (node (ref "C15") (pin "2") (pinfunction "2_2") (pintype "passive"))
      (node (ref "C16") (pin "2") (pinfunction "2_2") (pintype "passive"))
      (node (ref "C21") (pin "2") (pinfunction "2_2") (pintype "passive"))
      (node (ref "R25") (pin "2") (pinfunction "2_2") (pintype "passive"))
      (node (ref "U$12") (pin "VCC") (pinfunction "VCC_VCC") (pintype "bidirectional"))
      (node (ref "U$15") (pin "3.3V") (pinfunction "3.3V_3.3V") (pintype "bidirectional"))
      (node (ref "U$17") (pin "2") (pinfunction "VS_2") (pintype "bidirectional"))
      (node (ref "U$2") (pin "P13") (pinfunction "VDDA_P13") (pintype "bidirectional"))
      (node (ref "U$2") (pin "P19") (pinfunction "VDD4_P19") (pintype "bidirectional"))
      (node (ref "U$2") (pin "P32") (pinfunction "VDD1_P32") (pintype "bidirectional"))
      (node (ref "U$2") (pin "P48") (pinfunction "VDD2_P48") (pintype "bidirectional"))
      (node (ref "U$2") (pin "P64") (pinfunction "VDD3_P64") (pintype "bidirectional"))
    )
    (net (code "90") (name "unconnected-(F1-Pad2)") (class "Default")
      (node (ref "F1") (pin "2") (pinfunction "2_2") (pintype "bidirectional"))
    )
    (net (code "91") (name "unconnected-(R26-Pad2)") (class "Default")
      (node (ref "R26") (pin "2") (pinfunction "2_2") (pintype "passive"))
    )
    (net (code "92") (name "unconnected-(R27-Pad2)") (class "Default")
      (node (ref "R27") (pin "2") (pinfunction "2_2") (pintype "passive"))
    )
    (net (code "93") (name "unconnected-(U$15-PadANT)") (class "Default")
      (node (ref "U$15") (pin "ANT") (pinfunction "ANT_ANT") (pintype "bidirectional"))
    )
    (net (code "94") (name "unconnected-(U$15-PadDIO0)") (class "Default")
      (node (ref "U$15") (pin "DIO0") (pinfunction "DIO0_DIO0") (pintype "bidirectional"))
    )
    (net (code "95") (name "unconnected-(U$15-PadDIO2)") (class "Default")
      (node (ref "U$15") (pin "DIO2") (pinfunction "DIO2_DIO2") (pintype "bidirectional"))
    )
    (net (code "96") (name "unconnected-(U$15-PadDIO3)") (class "Default")
      (node (ref "U$15") (pin "DIO3") (pinfunction "DIO3_DIO3") (pintype "bidirectional"))
    )
    (net (code "97") (name "unconnected-(U$15-PadDIO4)") (class "Default")
      (node (ref "U$15") (pin "DIO4") (pinfunction "DIO4_DIO4") (pintype "bidirectional"))
    )
    (net (code "98") (name "unconnected-(U$15-PadDIO5)") (class "Default")
      (node (ref "U$15") (pin "DIO5") (pinfunction "DIO5_DIO5") (pintype "bidirectional"))
    )
  )
)
